# 06_SOM_CAM.net
KiCad netlist of a schematic drawn in Altium Designer
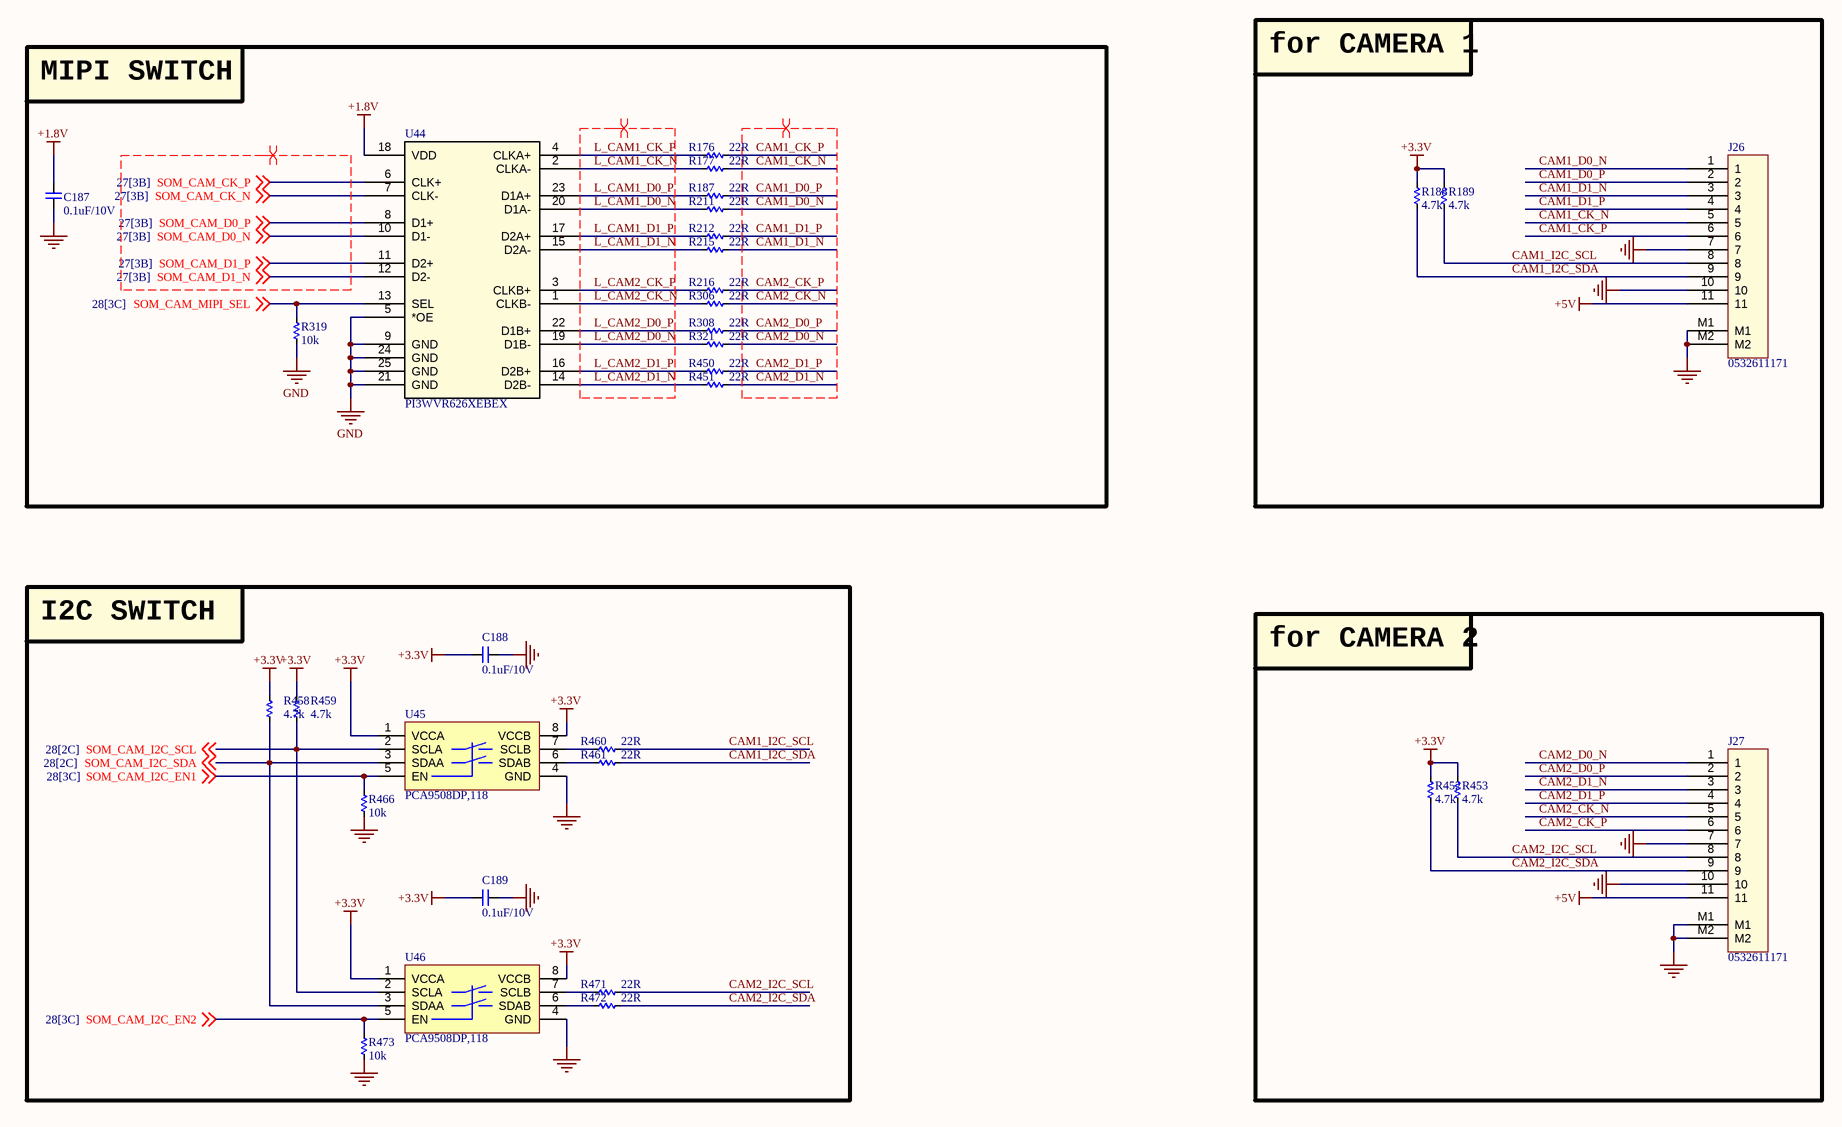
[diagram p0: 06_SOM_CAM.SchDoc]

(export (version "E")
  (design (tool "Eeschema 10.0.6"))
  (components
    (comp (ref "C187")
      (value "0.1uF/10V")
      (footprint "CAP_C_1005X60")
      (description "CAP CHIP")
      (libsource (lib "LABLIB") (part "_CAP_C_2"))
    )
    (comp (ref "C188")
      (value "0.1uF/10V")
      (footprint "CAP_C_1005X60")
      (description "CAP CHIP")
      (libsource (lib "LABLIB") (part "_CAP_C_2"))
    )
    (comp (ref "C189")
      (value "0.1uF/10V")
      (footprint "CAP_C_1005X60")
      (description "CAP CHIP")
      (libsource (lib "LABLIB") (part "_CAP_C_2"))
    )
    (comp (ref "J26")
      (value "0532611171")
      (footprint "MOLEX_0532611171")
      (libsource (lib "LABLIB") (part "Header 11x1_2M"))
    )
    (comp (ref "J27")
      (value "0532611171")
      (footprint "MOLEX_0532611171")
      (libsource (lib "LABLIB") (part "Header 11x1_2M"))
    )
    (comp (ref "R176")
      (value "22R")
      (footprint "RES_C_1005X40")
      (description "RES")
      (libsource (lib "LABLIB") (part "_RES_B_2"))
    )
    (comp (ref "R177")
      (value "22R")
      (footprint "RES_C_1005X40")
      (description "RES")
      (libsource (lib "LABLIB") (part "_RES_B_2"))
    )
    (comp (ref "R187")
      (value "22R")
      (footprint "RES_C_1005X40")
      (description "RES")
      (libsource (lib "LABLIB") (part "_RES_B_2"))
    )
    (comp (ref "R188")
      (value "4.7k")
      (footprint "RES_C_1005X40")
      (description "RES")
      (libsource (lib "LABLIB") (part "_RES_B_2"))
    )
    (comp (ref "R189")
      (value "4.7k")
      (footprint "RES_C_1005X40")
      (description "RES")
      (libsource (lib "LABLIB") (part "_RES_B_2"))
    )
    (comp (ref "R211")
      (value "22R")
      (footprint "RES_C_1005X40")
      (description "RES")
      (libsource (lib "LABLIB") (part "_RES_B_2"))
    )
    (comp (ref "R212")
      (value "22R")
      (footprint "RES_C_1005X40")
      (description "RES")
      (libsource (lib "LABLIB") (part "_RES_B_2"))
    )
    (comp (ref "R215")
      (value "22R")
      (footprint "RES_C_1005X40")
      (description "RES")
      (libsource (lib "LABLIB") (part "_RES_B_2"))
    )
    (comp (ref "R216")
      (value "22R")
      (footprint "RES_C_1005X40")
      (description "RES")
      (libsource (lib "LABLIB") (part "_RES_B_2"))
    )
    (comp (ref "R306")
      (value "22R")
      (footprint "RES_C_1005X40")
      (description "RES")
      (libsource (lib "LABLIB") (part "_RES_B_2"))
    )
    (comp (ref "R308")
      (value "22R")
      (footprint "RES_C_1005X40")
      (description "RES")
      (libsource (lib "LABLIB") (part "_RES_B_2"))
    )
    (comp (ref "R319")
      (value "10k")
      (footprint "RES_C_1005X40")
      (description "RES")
      (libsource (lib "LABLIB") (part "_RES_B_2"))
    )
    (comp (ref "R321")
      (value "22R")
      (footprint "RES_C_1005X40")
      (description "RES")
      (libsource (lib "LABLIB") (part "_RES_B_2"))
    )
    (comp (ref "R450")
      (value "22R")
      (footprint "RES_C_1005X40")
      (description "RES")
      (libsource (lib "LABLIB") (part "_RES_B_2"))
    )
    (comp (ref "R451")
      (value "22R")
      (footprint "RES_C_1005X40")
      (description "RES")
      (libsource (lib "LABLIB") (part "_RES_B_2"))
    )
    (comp (ref "R452")
      (value "4.7k")
      (footprint "RES_C_1005X40")
      (description "RES")
      (libsource (lib "LABLIB") (part "_RES_B_2"))
    )
    (comp (ref "R453")
      (value "4.7k")
      (footprint "RES_C_1005X40")
      (description "RES")
      (libsource (lib "LABLIB") (part "_RES_B_2"))
    )
    (comp (ref "R458")
      (value "4.7k")
      (footprint "RES_C_1005X40")
      (description "RES")
      (libsource (lib "LABLIB") (part "_RES_B_2"))
    )
    (comp (ref "R459")
      (value "4.7k")
      (footprint "RES_C_1005X40")
      (description "RES")
      (libsource (lib "LABLIB") (part "_RES_B_2"))
    )
    (comp (ref "R460")
      (value "22R")
      (footprint "RES_C_1005X40")
      (description "RES")
      (libsource (lib "LABLIB") (part "_RES_B_2"))
    )
    (comp (ref "R461")
      (value "22R")
      (footprint "RES_C_1005X40")
      (description "RES")
      (libsource (lib "LABLIB") (part "_RES_B_2"))
    )
    (comp (ref "R466")
      (value "10k")
      (footprint "RES_C_1005X40")
      (description "RES")
      (libsource (lib "LABLIB") (part "_RES_B_2"))
    )
    (comp (ref "R471")
      (value "22R")
      (footprint "RES_C_1005X40")
      (description "RES")
      (libsource (lib "LABLIB") (part "_RES_B_2"))
    )
    (comp (ref "R472")
      (value "22R")
      (footprint "RES_C_1005X40")
      (description "RES")
      (libsource (lib "LABLIB") (part "_RES_B_2"))
    )
    (comp (ref "R473")
      (value "10k")
      (footprint "RES_C_1005X40")
      (description "RES")
      (libsource (lib "LABLIB") (part "_RES_B_2"))
    )
    (comp (ref "U44")
      (value "PI3WVR626XEBEX")
      (footprint "PI3WVR626XEBEX_DIO")
      (libsource (lib "CAMERA_SchLib") (part "PI3WVR626XEBEX"))
    )
    (comp (ref "U45")
      (value "PCA9508DP,118")
      (footprint "TSOP8")
      (libsource (lib "EXP_HW_V3") (part "PCA9508DP,118"))
    )
    (comp (ref "U46")
      (value "PCA9508DP,118")
      (footprint "TSOP8")
      (libsource (lib "EXP_HW_V3") (part "PCA9508DP,118"))
    )
  )
  (nets
    (net (code "1") (name "+1.8V") (class "Default")
      (node (ref "C187") (pin "2") (pinfunction "2_2") (pintype "passive"))
      (node (ref "U44") (pin "18") (pinfunction "VDD_18") (pintype "passive"))
    )
    (net (code "2") (name "+3.3V") (class "Default")
      (node (ref "C188") (pin "2") (pinfunction "2_2") (pintype "passive"))
      (node (ref "C189") (pin "2") (pinfunction "2_2") (pintype "passive"))
      (node (ref "R188") (pin "1") (pinfunction "1_1") (pintype "passive"))
      (node (ref "R189") (pin "1") (pinfunction "1_1") (pintype "passive"))
      (node (ref "R452") (pin "1") (pinfunction "1_1") (pintype "passive"))
      (node (ref "R453") (pin "1") (pinfunction "1_1") (pintype "passive"))
      (node (ref "R458") (pin "1") (pinfunction "1_1") (pintype "passive"))
      (node (ref "R459") (pin "1") (pinfunction "1_1") (pintype "passive"))
      (node (ref "U45") (pin "1") (pinfunction "VCCA_1") (pintype "passive"))
      (node (ref "U45") (pin "8") (pinfunction "VCCB_8") (pintype "passive"))
      (node (ref "U46") (pin "1") (pinfunction "VCCA_1") (pintype "passive"))
      (node (ref "U46") (pin "8") (pinfunction "VCCB_8") (pintype "passive"))
    )
    (net (code "3") (name "+5V") (class "Default")
      (node (ref "J26") (pin "11") (pinfunction "11_11") (pintype "passive"))
      (node (ref "J27") (pin "11") (pinfunction "11_11") (pintype "passive"))
    )
    (net (code "4") (name "/CAM1_CK_N") (class "Default")
      (node (ref "J26") (pin "5") (pinfunction "5_5") (pintype "passive"))
      (node (ref "R177") (pin "2") (pinfunction "2_2") (pintype "passive"))
    )
    (net (code "5") (name "/CAM1_CK_P") (class "Default")
      (node (ref "J26") (pin "6") (pinfunction "6_6") (pintype "passive"))
      (node (ref "R176") (pin "2") (pinfunction "2_2") (pintype "passive"))
    )
    (net (code "6") (name "/CAM1_D0_N") (class "Default")
      (node (ref "J26") (pin "1") (pinfunction "1_1") (pintype "passive"))
      (node (ref "R211") (pin "2") (pinfunction "2_2") (pintype "passive"))
    )
    (net (code "7") (name "/CAM1_D0_P") (class "Default")
      (node (ref "J26") (pin "2") (pinfunction "2_2") (pintype "passive"))
      (node (ref "R187") (pin "2") (pinfunction "2_2") (pintype "passive"))
    )
    (net (code "8") (name "/CAM1_D1_N") (class "Default")
      (node (ref "J26") (pin "3") (pinfunction "3_3") (pintype "passive"))
      (node (ref "R215") (pin "2") (pinfunction "2_2") (pintype "passive"))
    )
    (net (code "9") (name "/CAM1_D1_P") (class "Default")
      (node (ref "J26") (pin "4") (pinfunction "4_4") (pintype "passive"))
      (node (ref "R212") (pin "2") (pinfunction "2_2") (pintype "passive"))
    )
    (net (code "10") (name "/CAM1_I2C_SCL") (class "Default")
      (node (ref "J26") (pin "8") (pinfunction "8_8") (pintype "passive"))
      (node (ref "R189") (pin "2") (pinfunction "2_2") (pintype "passive"))
      (node (ref "R460") (pin "2") (pinfunction "2_2") (pintype "passive"))
    )
    (net (code "11") (name "/CAM1_I2C_SDA") (class "Default")
      (node (ref "J26") (pin "9") (pinfunction "9_9") (pintype "passive"))
      (node (ref "R188") (pin "2") (pinfunction "2_2") (pintype "passive"))
      (node (ref "R461") (pin "2") (pinfunction "2_2") (pintype "passive"))
    )
    (net (code "12") (name "/CAM2_CK_N") (class "Default")
      (node (ref "J27") (pin "5") (pinfunction "5_5") (pintype "passive"))
      (node (ref "R306") (pin "2") (pinfunction "2_2") (pintype "passive"))
    )
    (net (code "13") (name "/CAM2_CK_P") (class "Default")
      (node (ref "J27") (pin "6") (pinfunction "6_6") (pintype "passive"))
      (node (ref "R216") (pin "2") (pinfunction "2_2") (pintype "passive"))
    )
    (net (code "14") (name "/CAM2_D0_N") (class "Default")
      (node (ref "J27") (pin "1") (pinfunction "1_1") (pintype "passive"))
      (node (ref "R321") (pin "2") (pinfunction "2_2") (pintype "passive"))
    )
    (net (code "15") (name "/CAM2_D0_P") (class "Default")
      (node (ref "J27") (pin "2") (pinfunction "2_2") (pintype "passive"))
      (node (ref "R308") (pin "2") (pinfunction "2_2") (pintype "passive"))
    )
    (net (code "16") (name "/CAM2_D1_N") (class "Default")
      (node (ref "J27") (pin "3") (pinfunction "3_3") (pintype "passive"))
      (node (ref "R451") (pin "2") (pinfunction "2_2") (pintype "passive"))
    )
    (net (code "17") (name "/CAM2_D1_P") (class "Default")
      (node (ref "J27") (pin "4") (pinfunction "4_4") (pintype "passive"))
      (node (ref "R450") (pin "2") (pinfunction "2_2") (pintype "passive"))
    )
    (net (code "18") (name "/CAM2_I2C_SCL") (class "Default")
      (node (ref "J27") (pin "8") (pinfunction "8_8") (pintype "passive"))
      (node (ref "R453") (pin "2") (pinfunction "2_2") (pintype "passive"))
      (node (ref "R471") (pin "2") (pinfunction "2_2") (pintype "passive"))
    )
    (net (code "19") (name "/CAM2_I2C_SDA") (class "Default")
      (node (ref "J27") (pin "9") (pinfunction "9_9") (pintype "passive"))
      (node (ref "R452") (pin "2") (pinfunction "2_2") (pintype "passive"))
      (node (ref "R472") (pin "2") (pinfunction "2_2") (pintype "passive"))
    )
    (net (code "20") (name "/L_CAM1_CK_N") (class "Default")
      (node (ref "R177") (pin "1") (pinfunction "1_1") (pintype "passive"))
      (node (ref "U44") (pin "2") (pinfunction "CLKA-_2") (pintype "passive"))
    )
    (net (code "21") (name "/L_CAM1_CK_P") (class "Default")
      (node (ref "R176") (pin "1") (pinfunction "1_1") (pintype "passive"))
      (node (ref "U44") (pin "4") (pinfunction "CLKA+_4") (pintype "passive"))
    )
    (net (code "22") (name "/L_CAM1_D0_N") (class "Default")
      (node (ref "R211") (pin "1") (pinfunction "1_1") (pintype "passive"))
      (node (ref "U44") (pin "20") (pinfunction "D1A-_20") (pintype "passive"))
    )
    (net (code "23") (name "/L_CAM1_D0_P") (class "Default")
      (node (ref "R187") (pin "1") (pinfunction "1_1") (pintype "passive"))
      (node (ref "U44") (pin "23") (pinfunction "D1A+_23") (pintype "passive"))
    )
    (net (code "24") (name "/L_CAM1_D1_N") (class "Default")
      (node (ref "R215") (pin "1") (pinfunction "1_1") (pintype "passive"))
      (node (ref "U44") (pin "15") (pinfunction "D2A-_15") (pintype "passive"))
    )
    (net (code "25") (name "/L_CAM1_D1_P") (class "Default")
      (node (ref "R212") (pin "1") (pinfunction "1_1") (pintype "passive"))
      (node (ref "U44") (pin "17") (pinfunction "D2A+_17") (pintype "passive"))
    )
    (net (code "26") (name "/L_CAM2_CK_N") (class "Default")
      (node (ref "R306") (pin "1") (pinfunction "1_1") (pintype "passive"))
      (node (ref "U44") (pin "1") (pinfunction "CLKB-_1") (pintype "passive"))
    )
    (net (code "27") (name "/L_CAM2_CK_P") (class "Default")
      (node (ref "R216") (pin "1") (pinfunction "1_1") (pintype "passive"))
      (node (ref "U44") (pin "3") (pinfunction "CLKB+_3") (pintype "passive"))
    )
    (net (code "28") (name "/L_CAM2_D0_N") (class "Default")
      (node (ref "R321") (pin "1") (pinfunction "1_1") (pintype "passive"))
      (node (ref "U44") (pin "19") (pinfunction "D1B-_19") (pintype "passive"))
    )
    (net (code "29") (name "/L_CAM2_D0_P") (class "Default")
      (node (ref "R308") (pin "1") (pinfunction "1_1") (pintype "passive"))
      (node (ref "U44") (pin "22") (pinfunction "D1B+_22") (pintype "passive"))
    )
    (net (code "30") (name "/L_CAM2_D1_N") (class "Default")
      (node (ref "R451") (pin "1") (pinfunction "1_1") (pintype "passive"))
      (node (ref "U44") (pin "14") (pinfunction "D2B-_14") (pintype "passive"))
    )
    (net (code "31") (name "/L_CAM2_D1_P") (class "Default")
      (node (ref "R450") (pin "1") (pinfunction "1_1") (pintype "passive"))
      (node (ref "U44") (pin "16") (pinfunction "D2B+_16") (pintype "passive"))
    )
    (net (code "32") (name "GND") (class "Default")
      (node (ref "C187") (pin "1") (pinfunction "1_1") (pintype "passive"))
      (node (ref "C188") (pin "1") (pinfunction "1_1") (pintype "passive"))
      (node (ref "C189") (pin "1") (pinfunction "1_1") (pintype "passive"))
      (node (ref "J26") (pin "10") (pinfunction "10_10") (pintype "passive"))
      (node (ref "J26") (pin "7") (pinfunction "7_7") (pintype "passive"))
      (node (ref "J26") (pin "M1") (pinfunction "M1_M1") (pintype "passive"))
      (node (ref "J26") (pin "M2") (pinfunction "M2_M2") (pintype "passive"))
      (node (ref "J27") (pin "10") (pinfunction "10_10") (pintype "passive"))
      (node (ref "J27") (pin "7") (pinfunction "7_7") (pintype "passive"))
      (node (ref "J27") (pin "M1") (pinfunction "M1_M1") (pintype "passive"))
      (node (ref "J27") (pin "M2") (pinfunction "M2_M2") (pintype "passive"))
      (node (ref "R319") (pin "1") (pinfunction "1_1") (pintype "passive"))
      (node (ref "R466") (pin "2") (pinfunction "2_2") (pintype "passive"))
      (node (ref "R473") (pin "2") (pinfunction "2_2") (pintype "passive"))
      (node (ref "U44") (pin "21") (pinfunction "GND_21") (pintype "passive"))
      (node (ref "U44") (pin "24") (pinfunction "GND_24") (pintype "passive"))
      (node (ref "U44") (pin "25") (pinfunction "GND_25") (pintype "passive"))
      (node (ref "U44") (pin "5") (pinfunction "*OE_5") (pintype "passive"))
      (node (ref "U44") (pin "9") (pinfunction "GND_9") (pintype "passive"))
      (node (ref "U45") (pin "4") (pinfunction "GND_4") (pintype "passive"))
      (node (ref "U46") (pin "4") (pinfunction "GND_4") (pintype "passive"))
    )
    (net (code "33") (name "Net-(U45-SCLB)") (class "Default")
      (node (ref "R460") (pin "1") (pinfunction "1_1") (pintype "passive"))
      (node (ref "U45") (pin "7") (pinfunction "SCLB_7") (pintype "passive"))
    )
    (net (code "34") (name "Net-(U45-SDAB)") (class "Default")
      (node (ref "R461") (pin "1") (pinfunction "1_1") (pintype "passive"))
      (node (ref "U45") (pin "6") (pinfunction "SDAB_6") (pintype "passive"))
    )
    (net (code "35") (name "Net-(U46-SCLB)") (class "Default")
      (node (ref "R471") (pin "1") (pinfunction "1_1") (pintype "passive"))
      (node (ref "U46") (pin "7") (pinfunction "SCLB_7") (pintype "passive"))
    )
    (net (code "36") (name "Net-(U46-SDAB)") (class "Default")
      (node (ref "R472") (pin "1") (pinfunction "1_1") (pintype "passive"))
      (node (ref "U46") (pin "6") (pinfunction "SDAB_6") (pintype "passive"))
    )
    (net (code "37") (name "SOM_CAM_CK_N") (class "Default")
      (node (ref "U44") (pin "7") (pinfunction "CLK-_7") (pintype "passive"))
    )
    (net (code "38") (name "SOM_CAM_CK_P") (class "Default")
      (node (ref "U44") (pin "6") (pinfunction "CLK+_6") (pintype "passive"))
    )
    (net (code "39") (name "SOM_CAM_D0_N") (class "Default")
      (node (ref "U44") (pin "10") (pinfunction "D1-_10") (pintype "passive"))
    )
    (net (code "40") (name "SOM_CAM_D0_P") (class "Default")
      (node (ref "U44") (pin "8") (pinfunction "D1+_8") (pintype "passive"))
    )
    (net (code "41") (name "SOM_CAM_D1_N") (class "Default")
      (node (ref "U44") (pin "12") (pinfunction "D2-_12") (pintype "passive"))
    )
    (net (code "42") (name "SOM_CAM_D1_P") (class "Default")
      (node (ref "U44") (pin "11") (pinfunction "D2+_11") (pintype "passive"))
    )
    (net (code "43") (name "SOM_CAM_I2C_EN1") (class "Default")
      (node (ref "R466") (pin "1") (pinfunction "1_1") (pintype "passive"))
      (node (ref "U45") (pin "5") (pinfunction "EN_5") (pintype "passive"))
    )
    (net (code "44") (name "SOM_CAM_I2C_EN2") (class "Default")
      (node (ref "R473") (pin "1") (pinfunction "1_1") (pintype "passive"))
      (node (ref "U46") (pin "5") (pinfunction "EN_5") (pintype "passive"))
    )
    (net (code "45") (name "SOM_CAM_I2C_SCL") (class "Default")
      (node (ref "R459") (pin "2") (pinfunction "2_2") (pintype "passive"))
      (node (ref "U45") (pin "2") (pinfunction "SCLA_2") (pintype "passive"))
      (node (ref "U46") (pin "2") (pinfunction "SCLA_2") (pintype "passive"))
    )
    (net (code "46") (name "SOM_CAM_I2C_SDA") (class "Default")
      (node (ref "R458") (pin "2") (pinfunction "2_2") (pintype "passive"))
      (node (ref "U45") (pin "3") (pinfunction "SDAA_3") (pintype "passive"))
      (node (ref "U46") (pin "3") (pinfunction "SDAA_3") (pintype "passive"))
    )
    (net (code "47") (name "SOM_CAM_MIPI_SEL") (class "Default")
      (node (ref "R319") (pin "2") (pinfunction "2_2") (pintype "passive"))
      (node (ref "U44") (pin "13") (pinfunction "SEL_13") (pintype "passive"))
    )
  )
)
